# openSX70_LENS_BELLOWS_V5_5-SEEED_2018051.net
KiCad netlist of a schematic drawn in EAGLE
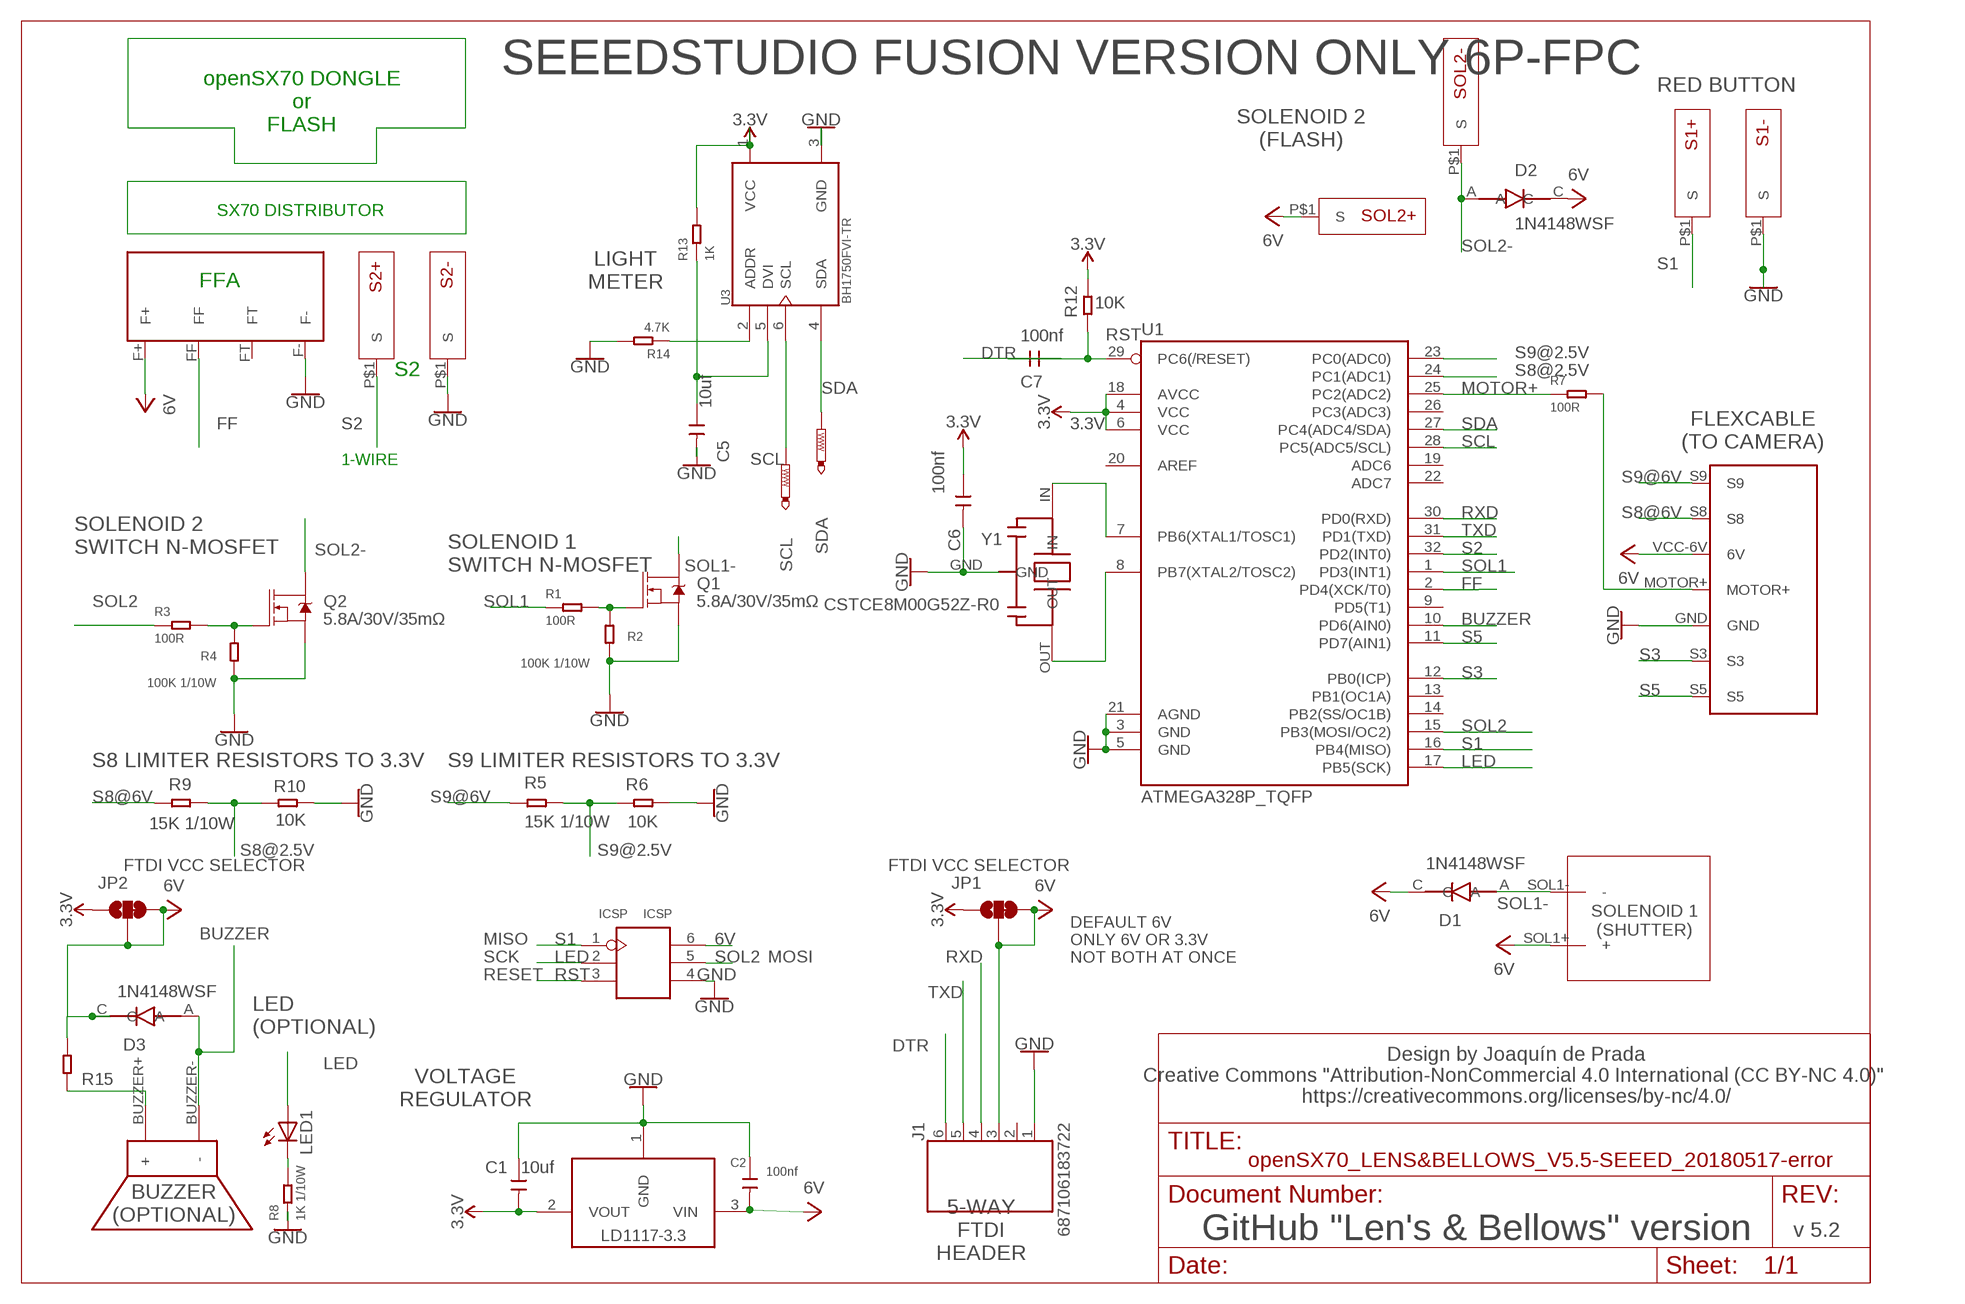
[diagram p0: schematic, sheet 1]

(export (version "E")
  (design (tool "Eeschema 10.0.6"))
  (components
    (comp (ref "C1")
      (value "10uf")
      (footprint "eagle-import:C0603")
      (fields (field (name "MPN") "CC0603KRX5R6BB106"))
      (libsource (lib "eagle-import") (part "CERAMIC-10UF-10V-10%-X5R(0603)"))
    )
    (comp (ref "C2")
      (value "100nf")
      (footprint "eagle-import:C0603")
      (fields (field (name "MPN") "CC0603KRX7R9BB104"))
      (libsource (lib "eagle-import") (part "CERAMIC-100NF-50V-10%-X7R(0603)"))
    )
    (comp (ref "C5")
      (value "10uf")
      (footprint "eagle-import:C0603")
      (fields (field (name "MPN") "CC0603KRX5R6BB106"))
      (libsource (lib "eagle-import") (part "CERAMIC-10UF-10V-10%-X5R(0603)"))
    )
    (comp (ref "C6")
      (value "100nf")
      (footprint "eagle-import:C0603")
      (fields (field (name "MPN") "CC0603KRX7R9BB104"))
      (libsource (lib "eagle-import") (part "CERAMIC-100NF-50V-10%-X7R(0603)"))
    )
    (comp (ref "C7")
      (value "100nf")
      (footprint "eagle-import:C0603")
      (fields (field (name "MPN") "CC0603KRX7R9BB104"))
      (libsource (lib "eagle-import") (part "CERAMIC-100NF-50V-10%-X7R(0603)"))
    )
    (comp (ref "D1")
      (value "1N4148WSF")
      (footprint "eagle-import:SODFL2512X100N")
      (fields (field (name "MANUFACTURER") "Fairchild Semiconductor"))
      (libsource (lib "eagle-import") (part "1N4148WS"))
    )
    (comp (ref "D2")
      (value "1N4148WSF")
      (footprint "eagle-import:SODFL2512X100N")
      (fields (field (name "MANUFACTURER") "Fairchild Semiconductor"))
      (libsource (lib "eagle-import") (part "1N4148WS"))
    )
    (comp (ref "D3")
      (value "1N4148WSF")
      (footprint "eagle-import:SODFL2512X100N")
      (fields (field (name "MANUFACTURER") "Fairchild Semiconductor"))
      (libsource (lib "eagle-import") (part "1N4148WS"))
    )
    (comp (ref "ICSP")
      (value "ICSP")
      (footprint "eagle-import:H2X3-2.54")
      (libsource (lib "eagle-import") (part "ICSP"))
    )
    (comp (ref "J1")
      (value "687106183722")
      (footprint "eagle-import:687106183722")
      (fields (field (name "MF") "Wurth Electronics"))
      (libsource (lib "eagle-import") (part "687106183722"))
    )
    (comp (ref "JP1")
      (value "FTDI VCC SELECTOR")
      (footprint "eagle-import:SMT-JUMPER_3_1-NC_TRACE_SILK")
      (libsource (lib "eagle-import") (part "JUMPER-SMT_3_1-NC_TRACE_SILK"))
    )
    (comp (ref "JP2")
      (value "FTDI VCC SELECTOR")
      (footprint "eagle-import:SMT-JUMPER_3_1-NC_TRACE_SILK")
      (libsource (lib "eagle-import") (part "JUMPER-SMT_3_1-NC_TRACE_SILK"))
    )
    (comp (ref "LD11172.5V")
      (value "LD1117 2.5V")
      (footprint "eagle-import:SOT223")
      (fields (field (name "MF") "Advanced Monolithic Systems") (field (name "MP") "AMS1117-5.0"))
      (libsource (lib "eagle-import") (part "LD1117-3.3"))
    )
    (comp (ref "LED1")
      (value "LEDCHIPLED_0805")
      (footprint "eagle-import:CHIPLED_0805")
      (libsource (lib "eagle-import") (part "LEDCHIPLED_0805"))
    )
    (comp (ref "Q1")
      (value "5.8A/30V/35mΩ")
      (footprint "eagle-import:SOT23-3")
      (libsource (lib "eagle-import") (part "MOSFET-NCH-AO3404A"))
    )
    (comp (ref "Q2")
      (value "5.8A/30V/35mΩ")
      (footprint "eagle-import:SOT23-3")
      (libsource (lib "eagle-import") (part "MOSFET-NCH-AO3404A"))
    )
    (comp (ref "R1")
      (value "100R")
      (footprint "eagle-import:R0603")
      (fields (field (name "MPN") "RC0603JR-07100RL"))
      (libsource (lib "eagle-import") (part "SMD-RES-100R-5%-1/10W(0603)"))
    )
    (comp (ref "R2")
      (value "100K 1/10W")
      (footprint "eagle-import:R0603")
      (fields (field (name "MPN") "RC0603JR-07100KL"))
      (libsource (lib "eagle-import") (part "SMD-RES-100K-5%-1/10W(0603)"))
    )
    (comp (ref "R3")
      (value "100R")
      (footprint "eagle-import:R0603")
      (fields (field (name "MPN") "RC0603JR-07100RL"))
      (libsource (lib "eagle-import") (part "SMD-RES-100R-5%-1/10W(0603)"))
    )
    (comp (ref "R4")
      (value "100K 1/10W")
      (footprint "eagle-import:R0603")
      (fields (field (name "MPN") "RC0603JR-07100KL"))
      (libsource (lib "eagle-import") (part "SMD-RES-100K-5%-1/10W(0603)"))
    )
    (comp (ref "R5")
      (value "15K 1/10W")
      (footprint "eagle-import:R0603")
      (fields (field (name "MPN") "RC0603FR-0715KL"))
      (libsource (lib "eagle-import") (part "SMD-RES-15K-1%-1/10W(0603)"))
    )
    (comp (ref "R6")
      (value "10K")
      (footprint "eagle-import:R0603")
      (fields (field (name "MPN") "RC0603FR-0710KL"))
      (libsource (lib "eagle-import") (part "SMD-RES-10K-1%-1/10W(0603)"))
    )
    (comp (ref "R7")
      (value "100R")
      (footprint "eagle-import:R0603")
      (fields (field (name "MPN") "RC0603JR-07100RL"))
      (libsource (lib "eagle-import") (part "SMD-RES-100R-5%-1/10W(0603)"))
    )
    (comp (ref "R8")
      (value "1K 1/10W")
      (footprint "eagle-import:R0603")
      (fields (field (name "MPN") "RC0603JR-071KL"))
      (libsource (lib "eagle-import") (part "SMD-RES-1K-5%-1/10W(0603)"))
    )
    (comp (ref "R9")
      (value "15K 1/10W")
      (footprint "eagle-import:R0603")
      (fields (field (name "MPN") "RC0603FR-0715KL"))
      (libsource (lib "eagle-import") (part "SMD-RES-15K-1%-1/10W(0603)"))
    )
    (comp (ref "R10")
      (value "10K")
      (footprint "eagle-import:R0603")
      (fields (field (name "MPN") "RC0603FR-0710KL"))
      (libsource (lib "eagle-import") (part "SMD-RES-10K-1%-1/10W(0603)"))
    )
    (comp (ref "R12")
      (value "10K")
      (footprint "eagle-import:R0603")
      (fields (field (name "MPN") "RC0603FR-0710KL"))
      (libsource (lib "eagle-import") (part "SMD-RES-10K-1%-1/10W(0603)"))
    )
    (comp (ref "R13")
      (value "1K")
      (footprint "eagle-import:R0603")
      (fields (field (name "MPN") "RC0603FR-071KL"))
      (libsource (lib "eagle-import") (part "SMD-RES-1K-1%-1/10W(0603)"))
    )
    (comp (ref "R14")
      (value "4.7K")
      (footprint "eagle-import:R0603")
      (fields (field (name "MPN") "RC0603JR-074K7L"))
      (libsource (lib "eagle-import") (part "SMD-RES-4.7K-5%-1/10W(0603)"))
    )
    (comp (ref "R15")
      (value "0R")
      (footprint "eagle-import:R0603")
      (fields (field (name "MPN") "RC0603JR-07100RL"))
      (libsource (lib "eagle-import") (part "SMD-RES-100R-5%-1/10W(0603)"))
    )
    (comp (ref "S1+")
      (value "SX70-S-PAD-NEW")
      (footprint "eagle-import:SX70-S-PAD2")
      (libsource (lib "eagle-import") (part "SX70-S-PAD-NEW"))
    )
    (comp (ref "S1-")
      (value "SX70-S-PAD-NEW")
      (footprint "eagle-import:SX70-S-PAD2")
      (libsource (lib "eagle-import") (part "SX70-S-PAD-NEW"))
    )
    (comp (ref "S2+")
      (value "SX70-S-PAD-NEW")
      (footprint "eagle-import:SX70-S-PAD2")
      (libsource (lib "eagle-import") (part "SX70-S-PAD-NEW"))
    )
    (comp (ref "S2-")
      (value "SX70-S-PAD-NEW")
      (footprint "eagle-import:SX70-S-PAD2")
      (libsource (lib "eagle-import") (part "SX70-S-PAD-NEW"))
    )
    (comp (ref "SCL")
      (value "PTR1TP08R")
      (footprint "eagle-import:TP08R")
      (libsource (lib "eagle-import") (part "PTR1TP08R"))
    )
    (comp (ref "SDA")
      (value "PTR1TP08R")
      (footprint "eagle-import:TP08R")
      (libsource (lib "eagle-import") (part "PTR1TP08R"))
    )
    (comp (ref "SOL1")
      (value "SX70-SOLENOID1-2PADS")
      (footprint "eagle-import:SX70-SOLENOID1-2")
      (libsource (lib "eagle-import") (part "SX70-SOLENOID1-2PADS"))
    )
    (comp (ref "SOL2+")
      (value "SX70-S-PAD-NEW")
      (footprint "eagle-import:SX70-S-PAD2")
      (libsource (lib "eagle-import") (part "SX70-S-PAD-NEW"))
    )
    (comp (ref "SOL2-")
      (value "SX70-S-PAD-NEW")
      (footprint "eagle-import:SX70-S-PAD2")
      (libsource (lib "eagle-import") (part "SX70-S-PAD-NEW"))
    )
    (comp (ref "U$1")
      (value "SX70-7-PAD")
      (footprint "eagle-import:SX70-7-PAD")
      (libsource (lib "eagle-import") (part "SX70-7-PAD"))
    )
    (comp (ref "U$2")
      (value "FFA")
      (footprint "eagle-import:FFA-PAD-PACKAGE")
      (libsource (lib "eagle-import") (part "SX70-FFA-PAD"))
    )
    (comp (ref "U$3")
      (value "CSET8-5G_V2")
      (footprint "eagle-import:CSET8-5G_PACKAGE")
      (libsource (lib "eagle-import") (part "CSET8-5G_V2"))
    )
    (comp (ref "U1")
      (value "ATMEGA328P_TQFP")
      (footprint "eagle-import:TQFP32-08")
      (libsource (lib "eagle-import") (part "ATMEGA328P_TQFP"))
    )
    (comp (ref "U3")
      (value "BH1750FVI-TR")
      (footprint "eagle-import:SOTFL50P300X75-6N")
      (fields (field (name "MF") "Rohm"))
      (libsource (lib "eagle-import") (part "BH1750FVI-TR"))
    )
    (comp (ref "Y1")
      (value "CSTCE8M00G52Z-R0")
      (footprint "eagle-import:CFP95P160X100-3N")
      (fields (field (name "MF") "Murata") (field (name "MP") "CSTCE16M0V53-R0"))
      (libsource (lib "eagle-import") (part "CSTCE16M0V53-R0"))
    )
  )
  (nets
    (net (code "1") (name "/BUZZER") (class "Default")
      (node (ref "D3") (pin "A") (pinfunction "A_A") (pintype "passive"))
      (node (ref "U$3") (pin "BUZZER-") (pinfunction "-_BUZZER-") (pintype "bidirectional"))
      (node (ref "U1") (pin "10") (pinfunction "PD6(AIN0)_10") (pintype "bidirectional"))
    )
    (net (code "2") (name "/DTR") (class "Default")
      (node (ref "C7") (pin "1") (pinfunction "1_1") (pintype "passive"))
      (node (ref "J1") (pin "6") (pinfunction "1_6") (pintype "passive"))
    )
    (net (code "3") (name "/FF") (class "Default")
      (node (ref "U$2") (pin "FF") (pinfunction "FF_FF") (pintype "bidirectional"))
      (node (ref "U1") (pin "2") (pinfunction "PD4(XCK/T0)_2") (pintype "bidirectional"))
    )
    (net (code "4") (name "/LED") (class "Default")
      (node (ref "ICSP") (pin "2") (pinfunction "SCK_2") (pintype "bidirectional"))
      (node (ref "LED1") (pin "A") (pinfunction "A_A") (pintype "passive"))
      (node (ref "U1") (pin "17") (pinfunction "PB5(SCK)_17") (pintype "bidirectional"))
    )
    (net (code "5") (name "/MOTOR+") (class "Default")
      (node (ref "R7") (pin "1") (pinfunction "1_1") (pintype "passive"))
      (node (ref "U1") (pin "25") (pinfunction "PC2(ADC2)_25") (pintype "bidirectional"))
    )
    (net (code "6") (name "/RST") (class "Default")
      (node (ref "C7") (pin "2") (pinfunction "2_2") (pintype "passive"))
      (node (ref "ICSP") (pin "3") (pinfunction "RST_3") (pintype "bidirectional"))
      (node (ref "R12") (pin "1") (pinfunction "1_1") (pintype "passive"))
      (node (ref "U1") (pin "29") (pinfunction "PC6(/RESET)_29") (pintype "bidirectional"))
    )
    (net (code "7") (name "/RXD") (class "Default")
      (node (ref "J1") (pin "4") (pinfunction "3_4") (pintype "passive"))
      (node (ref "U1") (pin "30") (pinfunction "PD0(RXD)_30") (pintype "bidirectional"))
    )
    (net (code "8") (name "/S1") (class "Default")
      (node (ref "ICSP") (pin "1") (pinfunction "MISO_1") (pintype "bidirectional"))
      (node (ref "S1+") (pin "P$1") (pinfunction "S_P$1") (pintype "bidirectional"))
      (node (ref "U1") (pin "16") (pinfunction "PB4(MISO)_16") (pintype "bidirectional"))
    )
    (net (code "9") (name "/S2") (class "Default")
      (node (ref "S2+") (pin "P$1") (pinfunction "S_P$1") (pintype "bidirectional"))
      (node (ref "U1") (pin "32") (pinfunction "PD2(INT0)_32") (pintype "bidirectional"))
    )
    (net (code "10") (name "/S3") (class "Default")
      (node (ref "U$1") (pin "S3") (pinfunction "S3_S3") (pintype "bidirectional"))
      (node (ref "U1") (pin "12") (pinfunction "PB0(ICP)_12") (pintype "bidirectional"))
    )
    (net (code "11") (name "/S5") (class "Default")
      (node (ref "U$1") (pin "S5") (pinfunction "S5_S5") (pintype "bidirectional"))
      (node (ref "U1") (pin "11") (pinfunction "PD7(AIN1)_11") (pintype "bidirectional"))
    )
    (net (code "12") (name "/S8@2.5V") (class "Default")
      (node (ref "R10") (pin "1") (pinfunction "1_1") (pintype "passive"))
      (node (ref "R9") (pin "2") (pinfunction "2_2") (pintype "passive"))
      (node (ref "U1") (pin "24") (pinfunction "PC1(ADC1)_24") (pintype "bidirectional"))
    )
    (net (code "13") (name "/S8@6V") (class "Default")
      (node (ref "R9") (pin "1") (pinfunction "1_1") (pintype "passive"))
      (node (ref "U$1") (pin "S8") (pinfunction "S8_S8") (pintype "bidirectional"))
    )
    (net (code "14") (name "/S9@2.5V") (class "Default")
      (node (ref "R5") (pin "2") (pinfunction "2_2") (pintype "passive"))
      (node (ref "R6") (pin "1") (pinfunction "1_1") (pintype "passive"))
      (node (ref "U1") (pin "23") (pinfunction "PC0(ADC0)_23") (pintype "bidirectional"))
    )
    (net (code "15") (name "/S9@6V") (class "Default")
      (node (ref "R5") (pin "1") (pinfunction "1_1") (pintype "passive"))
      (node (ref "U$1") (pin "S9") (pinfunction "S9_S9") (pintype "bidirectional"))
    )
    (net (code "16") (name "/SCL") (class "Default")
      (node (ref "SCL") (pin "TP") (pinfunction "TP_TP") (pintype "input"))
      (node (ref "U1") (pin "28") (pinfunction "PC5(ADC5/SCL)_28") (pintype "bidirectional"))
      (node (ref "U3") (pin "6") (pinfunction "SCL_6") (pintype "input"))
    )
    (net (code "17") (name "/SDA") (class "Default")
      (node (ref "SDA") (pin "TP") (pinfunction "TP_TP") (pintype "input"))
      (node (ref "U1") (pin "27") (pinfunction "PC4(ADC4/SDA)_27") (pintype "bidirectional"))
      (node (ref "U3") (pin "4") (pinfunction "SDA_4") (pintype "bidirectional"))
    )
    (net (code "18") (name "/SOL1") (class "Default")
      (node (ref "R1") (pin "1") (pinfunction "1_1") (pintype "passive"))
      (node (ref "U1") (pin "1") (pinfunction "PD3(INT1)_1") (pintype "bidirectional"))
    )
    (net (code "19") (name "/SOL1-") (class "Default")
      (node (ref "D1") (pin "A") (pinfunction "A_A") (pintype "passive"))
      (node (ref "Q1") (pin "3") (pinfunction "D_3") (pintype "bidirectional"))
      (node (ref "SOL1") (pin "SOL1-") (pinfunction "-_SOL1-") (pintype "bidirectional"))
    )
    (net (code "20") (name "/SOL2") (class "Default")
      (node (ref "ICSP") (pin "5") (pinfunction "MOSI_5") (pintype "bidirectional"))
      (node (ref "R3") (pin "1") (pinfunction "1_1") (pintype "passive"))
      (node (ref "U1") (pin "15") (pinfunction "PB3(MOSI/OC2)_15") (pintype "bidirectional"))
    )
    (net (code "21") (name "/SOL2-") (class "Default")
      (node (ref "D2") (pin "A") (pinfunction "A_A") (pintype "passive"))
      (node (ref "Q2") (pin "3") (pinfunction "D_3") (pintype "bidirectional"))
      (node (ref "SOL2-") (pin "P$1") (pinfunction "S_P$1") (pintype "bidirectional"))
    )
    (net (code "22") (name "/TXD") (class "Default")
      (node (ref "J1") (pin "5") (pinfunction "2_5") (pintype "passive"))
      (node (ref "U1") (pin "31") (pinfunction "PD1(TXD)_31") (pintype "bidirectional"))
    )
    (net (code "23") (name "3.3V") (class "Default")
      (node (ref "C1") (pin "2") (pinfunction "2_2") (pintype "passive"))
      (node (ref "C6") (pin "1") (pinfunction "1_1") (pintype "passive"))
      (node (ref "JP1") (pin "1") (pinfunction "1_1") (pintype "passive"))
      (node (ref "JP2") (pin "1") (pinfunction "1_1") (pintype "passive"))
      (node (ref "LD11172.5V") (pin "2") (pinfunction "VOUT_2") (pintype "bidirectional"))
      (node (ref "R12") (pin "2") (pinfunction "2_2") (pintype "passive"))
      (node (ref "R13") (pin "2") (pinfunction "2_2") (pintype "passive"))
      (node (ref "U1") (pin "18") (pinfunction "AVCC_18") (pintype "bidirectional"))
      (node (ref "U1") (pin "4") (pinfunction "VCC_4") (pintype "bidirectional"))
      (node (ref "U1") (pin "6") (pinfunction "VCC_6") (pintype "bidirectional"))
      (node (ref "U3") (pin "1") (pinfunction "VCC_1") (pintype "power_in"))
    )
    (net (code "24") (name "6V") (class "Default")
      (node (ref "C2") (pin "2") (pinfunction "2_2") (pintype "passive"))
      (node (ref "D1") (pin "C") (pinfunction "C_C") (pintype "passive"))
      (node (ref "D2") (pin "C") (pinfunction "C_C") (pintype "passive"))
      (node (ref "D3") (pin "C") (pinfunction "C_C") (pintype "passive"))
      (node (ref "ICSP") (pin "6") (pinfunction "VCC_6") (pintype "bidirectional"))
      (node (ref "J1") (pin "3") (pinfunction "4_3") (pintype "passive"))
      (node (ref "JP1") (pin "2") (pinfunction "2_2") (pintype "passive"))
      (node (ref "JP1") (pin "3") (pinfunction "3_3") (pintype "passive"))
      (node (ref "JP2") (pin "2") (pinfunction "2_2") (pintype "passive"))
      (node (ref "JP2") (pin "3") (pinfunction "3_3") (pintype "passive"))
      (node (ref "LD11172.5V") (pin "3") (pinfunction "VIN_3") (pintype "bidirectional"))
      (node (ref "R15") (pin "2") (pinfunction "2_2") (pintype "passive"))
      (node (ref "SOL1") (pin "SOL1+") (pinfunction "+_SOL1+") (pintype "bidirectional"))
      (node (ref "SOL2+") (pin "P$1") (pinfunction "S_P$1") (pintype "bidirectional"))
      (node (ref "U$1") (pin "VCC-6V") (pinfunction "6V_VCC-6V") (pintype "bidirectional"))
      (node (ref "U$2") (pin "F+") (pinfunction "F+_F+") (pintype "bidirectional"))
    )
    (net (code "25") (name "GND") (class "Default")
      (node (ref "C1") (pin "1") (pinfunction "1_1") (pintype "passive"))
      (node (ref "C2") (pin "1") (pinfunction "1_1") (pintype "passive"))
      (node (ref "C5") (pin "2") (pinfunction "2_2") (pintype "passive"))
      (node (ref "C6") (pin "2") (pinfunction "2_2") (pintype "passive"))
      (node (ref "ICSP") (pin "4") (pinfunction "GND_4") (pintype "bidirectional"))
      (node (ref "J1") (pin "1") (pinfunction "6_1") (pintype "passive"))
      (node (ref "LD11172.5V") (pin "1") (pinfunction "GND_1") (pintype "bidirectional"))
      (node (ref "Q1") (pin "2") (pinfunction "S_2") (pintype "bidirectional"))
      (node (ref "Q2") (pin "2") (pinfunction "S_2") (pintype "bidirectional"))
      (node (ref "R10") (pin "2") (pinfunction "2_2") (pintype "passive"))
      (node (ref "R14") (pin "2") (pinfunction "2_2") (pintype "passive"))
      (node (ref "R2") (pin "1") (pinfunction "1_1") (pintype "passive"))
      (node (ref "R4") (pin "1") (pinfunction "1_1") (pintype "passive"))
      (node (ref "R6") (pin "2") (pinfunction "2_2") (pintype "passive"))
      (node (ref "R8") (pin "1") (pinfunction "1_1") (pintype "passive"))
      (node (ref "S1-") (pin "P$1") (pinfunction "S_P$1") (pintype "bidirectional"))
      (node (ref "S2-") (pin "P$1") (pinfunction "S_P$1") (pintype "bidirectional"))
      (node (ref "U$1") (pin "GND") (pinfunction "GND_GND") (pintype "bidirectional"))
      (node (ref "U$2") (pin "F-") (pinfunction "F-_F-") (pintype "bidirectional"))
      (node (ref "U1") (pin "21") (pinfunction "AGND_21") (pintype "bidirectional"))
      (node (ref "U1") (pin "3") (pinfunction "GND_3") (pintype "bidirectional"))
      (node (ref "U1") (pin "5") (pinfunction "GND_5") (pintype "bidirectional"))
      (node (ref "U3") (pin "3") (pinfunction "GND_3") (pintype "power_in"))
      (node (ref "Y1") (pin "GND") (pinfunction "GND_GND") (pintype "passive"))
    )
    (net (code "26") (name "Net-(LED1-PadC)") (class "Default")
      (node (ref "LED1") (pin "C") (pinfunction "C_C") (pintype "passive"))
      (node (ref "R8") (pin "2") (pinfunction "2_2") (pintype "passive"))
    )
    (net (code "27") (name "Net-(Q1-G)") (class "Default")
      (node (ref "Q1") (pin "1") (pinfunction "G_1") (pintype "bidirectional"))
      (node (ref "R1") (pin "2") (pinfunction "2_2") (pintype "passive"))
      (node (ref "R2") (pin "2") (pinfunction "2_2") (pintype "passive"))
    )
    (net (code "28") (name "Net-(Q2-G)") (class "Default")
      (node (ref "Q2") (pin "1") (pinfunction "G_1") (pintype "bidirectional"))
      (node (ref "R3") (pin "2") (pinfunction "2_2") (pintype "passive"))
      (node (ref "R4") (pin "2") (pinfunction "2_2") (pintype "passive"))
    )
    (net (code "29") (name "Net-(R7-Pad2)") (class "Default")
      (node (ref "R7") (pin "2") (pinfunction "2_2") (pintype "passive"))
      (node (ref "U$1") (pin "MOTOR+") (pinfunction "MOTOR+_MOTOR+") (pintype "bidirectional"))
    )
    (net (code "30") (name "Net-(U$3-+)") (class "Default")
      (node (ref "R15") (pin "1") (pinfunction "1_1") (pintype "passive"))
      (node (ref "U$3") (pin "BUZZER+") (pinfunction "+_BUZZER+") (pintype "bidirectional"))
    )
    (net (code "31") (name "Net-(U1-PB6(XTAL1{slash}TOSC1))") (class "Default")
      (node (ref "U1") (pin "7") (pinfunction "PB6(XTAL1/TOSC1)_7") (pintype "bidirectional"))
      (node (ref "Y1") (pin "IN") (pinfunction "IN_IN") (pintype "input"))
    )
    (net (code "32") (name "Net-(U1-PB7(XTAL2{slash}TOSC2))") (class "Default")
      (node (ref "U1") (pin "8") (pinfunction "PB7(XTAL2/TOSC2)_8") (pintype "bidirectional"))
      (node (ref "Y1") (pin "OUT") (pinfunction "OUT_OUT") (pintype "output"))
    )
    (net (code "33") (name "Net-(U3-ADDR)") (class "Default")
      (node (ref "R14") (pin "1") (pinfunction "1_1") (pintype "passive"))
      (node (ref "U3") (pin "2") (pinfunction "ADDR_2") (pintype "input"))
    )
    (net (code "34") (name "Net-(U3-DVI)") (class "Default")
      (node (ref "C5") (pin "1") (pinfunction "1_1") (pintype "passive"))
      (node (ref "R13") (pin "1") (pinfunction "1_1") (pintype "passive"))
      (node (ref "U3") (pin "5") (pinfunction "DVI_5") (pintype "input"))
    )
    (net (code "35") (name "unconnected-(J1-5-Pad2)") (class "Default")
      (node (ref "J1") (pin "2") (pinfunction "5_2") (pintype "passive"))
    )
    (net (code "36") (name "unconnected-(U$2-PadFT)") (class "Default")
      (node (ref "U$2") (pin "FT") (pinfunction "FT_FT") (pintype "bidirectional"))
    )
    (net (code "37") (name "unconnected-(U1-ADC6-Pad19)") (class "Default")
      (node (ref "U1") (pin "19") (pinfunction "ADC6_19") (pintype "bidirectional"))
    )
    (net (code "38") (name "unconnected-(U1-ADC7-Pad22)") (class "Default")
      (node (ref "U1") (pin "22") (pinfunction "ADC7_22") (pintype "bidirectional"))
    )
    (net (code "39") (name "unconnected-(U1-AREF-Pad20)") (class "Default")
      (node (ref "U1") (pin "20") (pinfunction "AREF_20") (pintype "bidirectional"))
    )
    (net (code "40") (name "unconnected-(U1-PB1(OC1A)-Pad13)") (class "Default")
      (node (ref "U1") (pin "13") (pinfunction "PB1(OC1A)_13") (pintype "bidirectional"))
    )
    (net (code "41") (name "unconnected-(U1-PB2(SS{slash}OC1B)-Pad14)") (class "Default")
      (node (ref "U1") (pin "14") (pinfunction "PB2(SS/OC1B)_14") (pintype "bidirectional"))
    )
    (net (code "42") (name "unconnected-(U1-PC3(ADC3)-Pad26)") (class "Default")
      (node (ref "U1") (pin "26") (pinfunction "PC3(ADC3)_26") (pintype "bidirectional"))
    )
    (net (code "43") (name "unconnected-(U1-PD5(T1)-Pad9)") (class "Default")
      (node (ref "U1") (pin "9") (pinfunction "PD5(T1)_9") (pintype "bidirectional"))
    )
  )
)
